# Sheet2.net
KiCad netlist of a schematic drawn in Altium Designer
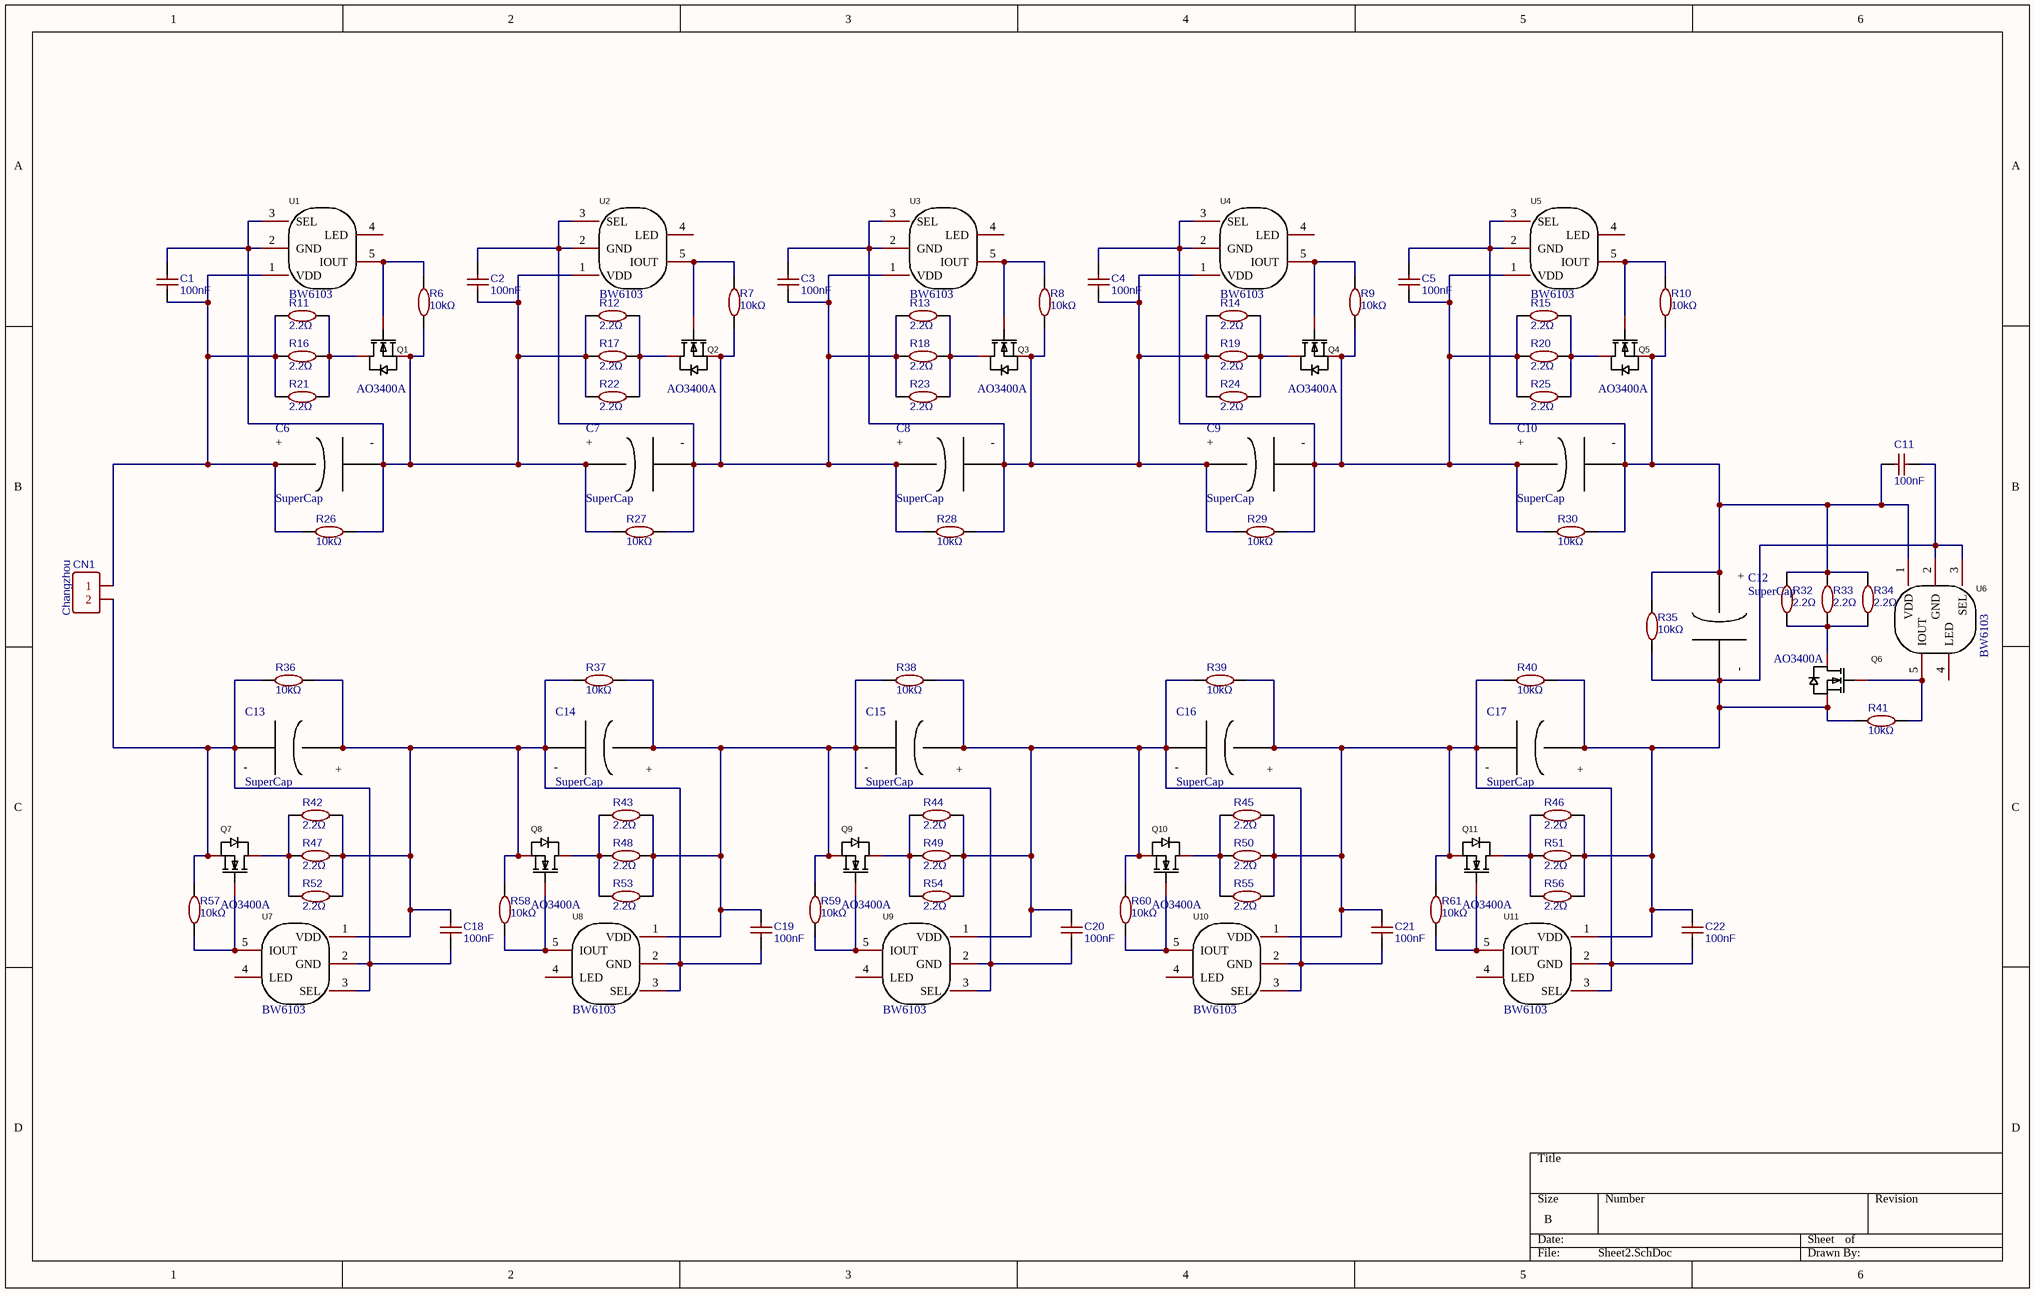
[diagram p0: Sheet2.SchDoc]

(export (version "E")
  (design (tool "Eeschema 10.0.6"))
  (components
    (comp (ref "C1")
      (value "100nF")
      (footprint "C-RAD-0603")
      (fields
        (field (name "BOM_SUPPLIER PART") "C157687")
        (field (name "BOM_MANUFACTURER PART") "0805CG330J500NT")
        (field (name "CONTRIBUTOR") "LCSC")
      )
      (libsource (lib "commonRC") (part "100nF"))
    )
    (comp (ref "C2")
      (value "100nF")
      (footprint "C-RAD-0603")
      (fields
        (field (name "BOM_SUPPLIER PART") "C157687")
        (field (name "BOM_MANUFACTURER PART") "0805CG330J500NT")
        (field (name "CONTRIBUTOR") "LCSC")
      )
      (libsource (lib "commonRC") (part "100nF"))
    )
    (comp (ref "C3")
      (value "100nF")
      (footprint "C-RAD-0603")
      (fields
        (field (name "BOM_SUPPLIER PART") "C157687")
        (field (name "BOM_MANUFACTURER PART") "0805CG330J500NT")
        (field (name "CONTRIBUTOR") "LCSC")
      )
      (libsource (lib "commonRC") (part "100nF"))
    )
    (comp (ref "C4")
      (value "100nF")
      (footprint "C-RAD-0603")
      (fields
        (field (name "BOM_SUPPLIER PART") "C157687")
        (field (name "BOM_MANUFACTURER PART") "0805CG330J500NT")
        (field (name "CONTRIBUTOR") "LCSC")
      )
      (libsource (lib "commonRC") (part "100nF"))
    )
    (comp (ref "C5")
      (value "100nF")
      (footprint "C-RAD-0603")
      (fields
        (field (name "BOM_SUPPLIER PART") "C157687")
        (field (name "BOM_MANUFACTURER PART") "0805CG330J500NT")
        (field (name "CONTRIBUTOR") "LCSC")
      )
      (libsource (lib "commonRC") (part "100nF"))
    )
    (comp (ref "C6")
      (value "SuperCap")
      (footprint "C_supercap1")
      (libsource (lib "Schlib1") (part "50F 2.7v"))
    )
    (comp (ref "C7")
      (value "SuperCap")
      (footprint "C_supercap1")
      (libsource (lib "Schlib1") (part "50F 2.7v"))
    )
    (comp (ref "C8")
      (value "SuperCap")
      (footprint "C_supercap1")
      (libsource (lib "Schlib1") (part "50F 2.7v"))
    )
    (comp (ref "C9")
      (value "SuperCap")
      (footprint "C_supercap1")
      (libsource (lib "Schlib1") (part "50F 2.7v"))
    )
    (comp (ref "C10")
      (value "SuperCap")
      (footprint "C_supercap1")
      (libsource (lib "Schlib1") (part "50F 2.7v"))
    )
    (comp (ref "C11")
      (value "100nF")
      (footprint "C-RAD-0603")
      (fields
        (field (name "BOM_SUPPLIER PART") "C157687")
        (field (name "BOM_MANUFACTURER PART") "0805CG330J500NT")
        (field (name "CONTRIBUTOR") "LCSC")
      )
      (libsource (lib "commonRC") (part "100nF"))
    )
    (comp (ref "C12") (value "SuperCap") (footprint "C_supercap1") (libsource (lib "") (part "50F 2.7v_1")))
    (comp (ref "C13")
      (value "SuperCap")
      (footprint "C_supercap1")
      (libsource (lib "Schlib1") (part "50F 2.7v"))
    )
    (comp (ref "C14")
      (value "SuperCap")
      (footprint "C_supercap1")
      (libsource (lib "Schlib1") (part "50F 2.7v"))
    )
    (comp (ref "C15")
      (value "SuperCap")
      (footprint "C_supercap1")
      (libsource (lib "Schlib1") (part "50F 2.7v"))
    )
    (comp (ref "C16")
      (value "SuperCap")
      (footprint "C_supercap1")
      (libsource (lib "Schlib1") (part "50F 2.7v"))
    )
    (comp (ref "C17")
      (value "SuperCap")
      (footprint "C_supercap1")
      (libsource (lib "Schlib1") (part "50F 2.7v"))
    )
    (comp (ref "C18")
      (value "100nF")
      (footprint "C-RAD-0603")
      (fields
        (field (name "BOM_SUPPLIER PART") "C157687")
        (field (name "BOM_MANUFACTURER PART") "0805CG330J500NT")
        (field (name "CONTRIBUTOR") "LCSC")
      )
      (libsource (lib "commonRC") (part "100nF"))
    )
    (comp (ref "C19")
      (value "100nF")
      (footprint "C-RAD-0603")
      (fields
        (field (name "BOM_SUPPLIER PART") "C157687")
        (field (name "BOM_MANUFACTURER PART") "0805CG330J500NT")
        (field (name "CONTRIBUTOR") "LCSC")
      )
      (libsource (lib "commonRC") (part "100nF"))
    )
    (comp (ref "C20")
      (value "100nF")
      (footprint "C-RAD-0603")
      (fields
        (field (name "BOM_SUPPLIER PART") "C157687")
        (field (name "BOM_MANUFACTURER PART") "0805CG330J500NT")
        (field (name "CONTRIBUTOR") "LCSC")
      )
      (libsource (lib "commonRC") (part "100nF"))
    )
    (comp (ref "C21")
      (value "100nF")
      (footprint "C-RAD-0603")
      (fields
        (field (name "BOM_SUPPLIER PART") "C157687")
        (field (name "BOM_MANUFACTURER PART") "0805CG330J500NT")
        (field (name "CONTRIBUTOR") "LCSC")
      )
      (libsource (lib "commonRC") (part "100nF"))
    )
    (comp (ref "C22")
      (value "100nF")
      (footprint "C-RAD-0603")
      (fields
        (field (name "BOM_SUPPLIER PART") "C157687")
        (field (name "BOM_MANUFACTURER PART") "0805CG330J500NT")
        (field (name "CONTRIBUTOR") "LCSC")
      )
      (libsource (lib "commonRC") (part "100nF"))
    )
    (comp (ref "CN1")
      (value "Changzhou")
      (footprint "CONN-TH_XT30UPB-F")
      (fields
        (field (name "BOM_SUPPLIER PART") "C108769")
        (field (name "BOM_MANUFACTURER PART") "XT30UPB-F")
        (field (name "CONTRIBUTOR") "LCSC")
      )
      (libsource (lib "Schlib1") (part "Changzhou"))
    )
    (comp (ref "Q1")
      (value "AO3400A")
      (footprint "SOT-23")
      (fields (field (name "MANUFACTURER") "AOS"))
      (libsource (lib "Schlib1") (part "AO3400A_C20917"))
    )
    (comp (ref "Q2")
      (value "AO3400A")
      (footprint "SOT-23")
      (fields (field (name "MANUFACTURER") "AOS"))
      (libsource (lib "Schlib1") (part "AO3400A_C20917"))
    )
    (comp (ref "Q3")
      (value "AO3400A")
      (footprint "SOT-23")
      (fields (field (name "MANUFACTURER") "AOS"))
      (libsource (lib "Schlib1") (part "AO3400A_C20917"))
    )
    (comp (ref "Q4")
      (value "AO3400A")
      (footprint "SOT-23")
      (fields (field (name "MANUFACTURER") "AOS"))
      (libsource (lib "Schlib1") (part "AO3400A_C20917"))
    )
    (comp (ref "Q5")
      (value "AO3400A")
      (footprint "SOT-23")
      (fields (field (name "MANUFACTURER") "AOS"))
      (libsource (lib "Schlib1") (part "AO3400A_C20917"))
    )
    (comp (ref "Q6")
      (value "AO3400A")
      (footprint "SOT-23")
      (fields (field (name "MANUFACTURER") "AOS"))
      (libsource (lib "Schlib1") (part "AO3400A_C20917"))
    )
    (comp (ref "Q7")
      (value "AO3400A")
      (footprint "SOT-23")
      (fields (field (name "MANUFACTURER") "AOS"))
      (libsource (lib "Schlib1") (part "AO3400A_C20917"))
    )
    (comp (ref "Q8")
      (value "AO3400A")
      (footprint "SOT-23")
      (fields (field (name "MANUFACTURER") "AOS"))
      (libsource (lib "Schlib1") (part "AO3400A_C20917"))
    )
    (comp (ref "Q9")
      (value "AO3400A")
      (footprint "SOT-23")
      (fields (field (name "MANUFACTURER") "AOS"))
      (libsource (lib "Schlib1") (part "AO3400A_C20917"))
    )
    (comp (ref "Q10")
      (value "AO3400A")
      (footprint "SOT-23")
      (fields (field (name "MANUFACTURER") "AOS"))
      (libsource (lib "Schlib1") (part "AO3400A_C20917"))
    )
    (comp (ref "Q11")
      (value "AO3400A")
      (footprint "SOT-23")
      (fields (field (name "MANUFACTURER") "AOS"))
      (libsource (lib "Schlib1") (part "AO3400A_C20917"))
    )
    (comp (ref "R6")
      (value "10kΩ")
      (footprint "0603-1")
      (fields
        (field (name "BOM_MANUFACTURER PART") "0603WAF1002T5E")
        (field (name "BOM_SUPPLIER PART") "C25804")
      )
      (libsource (lib "commonRC") (part "10kΩ"))
    )
    (comp (ref "R7")
      (value "10kΩ")
      (footprint "0603-1")
      (fields
        (field (name "BOM_MANUFACTURER PART") "0603WAF1002T5E")
        (field (name "BOM_SUPPLIER PART") "C25804")
      )
      (libsource (lib "commonRC") (part "10kΩ"))
    )
    (comp (ref "R8")
      (value "10kΩ")
      (footprint "0603-1")
      (fields
        (field (name "BOM_MANUFACTURER PART") "0603WAF1002T5E")
        (field (name "BOM_SUPPLIER PART") "C25804")
      )
      (libsource (lib "commonRC") (part "10kΩ"))
    )
    (comp (ref "R9")
      (value "10kΩ")
      (footprint "0603-1")
      (fields
        (field (name "BOM_MANUFACTURER PART") "0603WAF1002T5E")
        (field (name "BOM_SUPPLIER PART") "C25804")
      )
      (libsource (lib "commonRC") (part "10kΩ"))
    )
    (comp (ref "R10")
      (value "10kΩ")
      (footprint "0603-1")
      (fields
        (field (name "BOM_MANUFACTURER PART") "0603WAF1002T5E")
        (field (name "BOM_SUPPLIER PART") "C25804")
      )
      (libsource (lib "commonRC") (part "10kΩ"))
    )
    (comp (ref "R11")
      (value "2.2Ω")
      (footprint "2512")
      (fields
        (field (name "BOM_MANUFACTURER PART") "0603WAF1002T5E")
        (field (name "BOM_SUPPLIER PART") "C25804")
      )
      (libsource (lib "Schlib1") (part "2.2Ω_2512"))
    )
    (comp (ref "R12")
      (value "2.2Ω")
      (footprint "2512")
      (fields
        (field (name "BOM_MANUFACTURER PART") "0603WAF1002T5E")
        (field (name "BOM_SUPPLIER PART") "C25804")
      )
      (libsource (lib "Schlib1") (part "2.2Ω_2512"))
    )
    (comp (ref "R13")
      (value "2.2Ω")
      (footprint "2512")
      (fields
        (field (name "BOM_MANUFACTURER PART") "0603WAF1002T5E")
        (field (name "BOM_SUPPLIER PART") "C25804")
      )
      (libsource (lib "Schlib1") (part "2.2Ω_2512"))
    )
    (comp (ref "R14")
      (value "2.2Ω")
      (footprint "2512")
      (fields
        (field (name "BOM_MANUFACTURER PART") "0603WAF1002T5E")
        (field (name "BOM_SUPPLIER PART") "C25804")
      )
      (libsource (lib "Schlib1") (part "2.2Ω_2512"))
    )
    (comp (ref "R15")
      (value "2.2Ω")
      (footprint "2512")
      (fields
        (field (name "BOM_MANUFACTURER PART") "0603WAF1002T5E")
        (field (name "BOM_SUPPLIER PART") "C25804")
      )
      (libsource (lib "Schlib1") (part "2.2Ω_2512"))
    )
    (comp (ref "R16")
      (value "2.2Ω")
      (footprint "2512")
      (fields
        (field (name "BOM_MANUFACTURER PART") "0603WAF1002T5E")
        (field (name "BOM_SUPPLIER PART") "C25804")
      )
      (libsource (lib "Schlib1") (part "2.2Ω_2512"))
    )
    (comp (ref "R17")
      (value "2.2Ω")
      (footprint "2512")
      (fields
        (field (name "BOM_MANUFACTURER PART") "0603WAF1002T5E")
        (field (name "BOM_SUPPLIER PART") "C25804")
      )
      (libsource (lib "Schlib1") (part "2.2Ω_2512"))
    )
    (comp (ref "R18")
      (value "2.2Ω")
      (footprint "2512")
      (fields
        (field (name "BOM_MANUFACTURER PART") "0603WAF1002T5E")
        (field (name "BOM_SUPPLIER PART") "C25804")
      )
      (libsource (lib "Schlib1") (part "2.2Ω_2512"))
    )
    (comp (ref "R19")
      (value "2.2Ω")
      (footprint "2512")
      (fields
        (field (name "BOM_MANUFACTURER PART") "0603WAF1002T5E")
        (field (name "BOM_SUPPLIER PART") "C25804")
      )
      (libsource (lib "Schlib1") (part "2.2Ω_2512"))
    )
    (comp (ref "R20")
      (value "2.2Ω")
      (footprint "2512")
      (fields
        (field (name "BOM_MANUFACTURER PART") "0603WAF1002T5E")
        (field (name "BOM_SUPPLIER PART") "C25804")
      )
      (libsource (lib "Schlib1") (part "2.2Ω_2512"))
    )
    (comp (ref "R21")
      (value "2.2Ω")
      (footprint "2512")
      (fields
        (field (name "BOM_MANUFACTURER PART") "0603WAF1002T5E")
        (field (name "BOM_SUPPLIER PART") "C25804")
      )
      (libsource (lib "Schlib1") (part "2.2Ω_2512"))
    )
    (comp (ref "R22")
      (value "2.2Ω")
      (footprint "2512")
      (fields
        (field (name "BOM_MANUFACTURER PART") "0603WAF1002T5E")
        (field (name "BOM_SUPPLIER PART") "C25804")
      )
      (libsource (lib "Schlib1") (part "2.2Ω_2512"))
    )
    (comp (ref "R23")
      (value "2.2Ω")
      (footprint "2512")
      (fields
        (field (name "BOM_MANUFACTURER PART") "0603WAF1002T5E")
        (field (name "BOM_SUPPLIER PART") "C25804")
      )
      (libsource (lib "Schlib1") (part "2.2Ω_2512"))
    )
    (comp (ref "R24")
      (value "2.2Ω")
      (footprint "2512")
      (fields
        (field (name "BOM_MANUFACTURER PART") "0603WAF1002T5E")
        (field (name "BOM_SUPPLIER PART") "C25804")
      )
      (libsource (lib "Schlib1") (part "2.2Ω_2512"))
    )
    (comp (ref "R25")
      (value "2.2Ω")
      (footprint "2512")
      (fields
        (field (name "BOM_MANUFACTURER PART") "0603WAF1002T5E")
        (field (name "BOM_SUPPLIER PART") "C25804")
      )
      (libsource (lib "Schlib1") (part "2.2Ω_2512"))
    )
    (comp (ref "R26")
      (value "10kΩ")
      (footprint "0603-1")
      (fields
        (field (name "BOM_MANUFACTURER PART") "0603WAF1002T5E")
        (field (name "BOM_SUPPLIER PART") "C25804")
      )
      (libsource (lib "commonRC") (part "10kΩ"))
    )
    (comp (ref "R27")
      (value "10kΩ")
      (footprint "0603-1")
      (fields
        (field (name "BOM_MANUFACTURER PART") "0603WAF1002T5E")
        (field (name "BOM_SUPPLIER PART") "C25804")
      )
      (libsource (lib "commonRC") (part "10kΩ"))
    )
    (comp (ref "R28")
      (value "10kΩ")
      (footprint "0603-1")
      (fields
        (field (name "BOM_MANUFACTURER PART") "0603WAF1002T5E")
        (field (name "BOM_SUPPLIER PART") "C25804")
      )
      (libsource (lib "commonRC") (part "10kΩ"))
    )
    (comp (ref "R29")
      (value "10kΩ")
      (footprint "0603-1")
      (fields
        (field (name "BOM_MANUFACTURER PART") "0603WAF1002T5E")
        (field (name "BOM_SUPPLIER PART") "C25804")
      )
      (libsource (lib "commonRC") (part "10kΩ"))
    )
    (comp (ref "R30")
      (value "10kΩ")
      (footprint "0603-1")
      (fields
        (field (name "BOM_MANUFACTURER PART") "0603WAF1002T5E")
        (field (name "BOM_SUPPLIER PART") "C25804")
      )
      (libsource (lib "commonRC") (part "10kΩ"))
    )
    (comp (ref "R32")
      (value "2.2Ω")
      (footprint "2512")
      (fields
        (field (name "BOM_MANUFACTURER PART") "0603WAF1002T5E")
        (field (name "BOM_SUPPLIER PART") "C25804")
      )
      (libsource (lib "Schlib1") (part "2.2Ω_2512"))
    )
    (comp (ref "R33")
      (value "2.2Ω")
      (footprint "2512")
      (fields
        (field (name "BOM_MANUFACTURER PART") "0603WAF1002T5E")
        (field (name "BOM_SUPPLIER PART") "C25804")
      )
      (libsource (lib "Schlib1") (part "2.2Ω_2512"))
    )
    (comp (ref "R34")
      (value "2.2Ω")
      (footprint "2512")
      (fields
        (field (name "BOM_MANUFACTURER PART") "0603WAF1002T5E")
        (field (name "BOM_SUPPLIER PART") "C25804")
      )
      (libsource (lib "Schlib1") (part "2.2Ω_2512"))
    )
    (comp (ref "R35")
      (value "10kΩ")
      (footprint "0603-1")
      (fields
        (field (name "BOM_MANUFACTURER PART") "0603WAF1002T5E")
        (field (name "BOM_SUPPLIER PART") "C25804")
      )
      (libsource (lib "commonRC") (part "10kΩ"))
    )
    (comp (ref "R36")
      (value "10kΩ")
      (footprint "0603-1")
      (fields
        (field (name "BOM_MANUFACTURER PART") "0603WAF1002T5E")
        (field (name "BOM_SUPPLIER PART") "C25804")
      )
      (libsource (lib "commonRC") (part "10kΩ"))
    )
    (comp (ref "R37")
      (value "10kΩ")
      (footprint "0603-1")
      (fields
        (field (name "BOM_MANUFACTURER PART") "0603WAF1002T5E")
        (field (name "BOM_SUPPLIER PART") "C25804")
      )
      (libsource (lib "commonRC") (part "10kΩ"))
    )
    (comp (ref "R38")
      (value "10kΩ")
      (footprint "0603-1")
      (fields
        (field (name "BOM_MANUFACTURER PART") "0603WAF1002T5E")
        (field (name "BOM_SUPPLIER PART") "C25804")
      )
      (libsource (lib "commonRC") (part "10kΩ"))
    )
    (comp (ref "R39")
      (value "10kΩ")
      (footprint "0603-1")
      (fields
        (field (name "BOM_MANUFACTURER PART") "0603WAF1002T5E")
        (field (name "BOM_SUPPLIER PART") "C25804")
      )
      (libsource (lib "commonRC") (part "10kΩ"))
    )
    (comp (ref "R40")
      (value "10kΩ")
      (footprint "0603-1")
      (fields
        (field (name "BOM_MANUFACTURER PART") "0603WAF1002T5E")
        (field (name "BOM_SUPPLIER PART") "C25804")
      )
      (libsource (lib "commonRC") (part "10kΩ"))
    )
    (comp (ref "R41")
      (value "10kΩ")
      (footprint "0603-1")
      (fields
        (field (name "BOM_MANUFACTURER PART") "0603WAF1002T5E")
        (field (name "BOM_SUPPLIER PART") "C25804")
      )
      (libsource (lib "commonRC") (part "10kΩ"))
    )
    (comp (ref "R42")
      (value "2.2Ω")
      (footprint "2512")
      (fields
        (field (name "BOM_MANUFACTURER PART") "0603WAF1002T5E")
        (field (name "BOM_SUPPLIER PART") "C25804")
      )
      (libsource (lib "Schlib1") (part "2.2Ω_2512"))
    )
    (comp (ref "R43")
      (value "2.2Ω")
      (footprint "2512")
      (fields
        (field (name "BOM_MANUFACTURER PART") "0603WAF1002T5E")
        (field (name "BOM_SUPPLIER PART") "C25804")
      )
      (libsource (lib "Schlib1") (part "2.2Ω_2512"))
    )
    (comp (ref "R44")
      (value "2.2Ω")
      (footprint "2512")
      (fields
        (field (name "BOM_MANUFACTURER PART") "0603WAF1002T5E")
        (field (name "BOM_SUPPLIER PART") "C25804")
      )
      (libsource (lib "Schlib1") (part "2.2Ω_2512"))
    )
    (comp (ref "R45")
      (value "2.2Ω")
      (footprint "2512")
      (fields
        (field (name "BOM_MANUFACTURER PART") "0603WAF1002T5E")
        (field (name "BOM_SUPPLIER PART") "C25804")
      )
      (libsource (lib "Schlib1") (part "2.2Ω_2512"))
    )
    (comp (ref "R46")
      (value "2.2Ω")
      (footprint "2512")
      (fields
        (field (name "BOM_MANUFACTURER PART") "0603WAF1002T5E")
        (field (name "BOM_SUPPLIER PART") "C25804")
      )
      (libsource (lib "Schlib1") (part "2.2Ω_2512"))
    )
    (comp (ref "R47")
      (value "2.2Ω")
      (footprint "2512")
      (fields
        (field (name "BOM_MANUFACTURER PART") "0603WAF1002T5E")
        (field (name "BOM_SUPPLIER PART") "C25804")
      )
      (libsource (lib "Schlib1") (part "2.2Ω_2512"))
    )
    (comp (ref "R48")
      (value "2.2Ω")
      (footprint "2512")
      (fields
        (field (name "BOM_MANUFACTURER PART") "0603WAF1002T5E")
        (field (name "BOM_SUPPLIER PART") "C25804")
      )
      (libsource (lib "Schlib1") (part "2.2Ω_2512"))
    )
    (comp (ref "R49")
      (value "2.2Ω")
      (footprint "2512")
      (fields
        (field (name "BOM_MANUFACTURER PART") "0603WAF1002T5E")
        (field (name "BOM_SUPPLIER PART") "C25804")
      )
      (libsource (lib "Schlib1") (part "2.2Ω_2512"))
    )
    (comp (ref "R50")
      (value "2.2Ω")
      (footprint "2512")
      (fields
        (field (name "BOM_MANUFACTURER PART") "0603WAF1002T5E")
        (field (name "BOM_SUPPLIER PART") "C25804")
      )
      (libsource (lib "Schlib1") (part "2.2Ω_2512"))
    )
    (comp (ref "R51")
      (value "2.2Ω")
      (footprint "2512")
      (fields
        (field (name "BOM_MANUFACTURER PART") "0603WAF1002T5E")
        (field (name "BOM_SUPPLIER PART") "C25804")
      )
      (libsource (lib "Schlib1") (part "2.2Ω_2512"))
    )
    (comp (ref "R52")
      (value "2.2Ω")
      (footprint "2512")
      (fields
        (field (name "BOM_MANUFACTURER PART") "0603WAF1002T5E")
        (field (name "BOM_SUPPLIER PART") "C25804")
      )
      (libsource (lib "Schlib1") (part "2.2Ω_2512"))
    )
    (comp (ref "R53")
      (value "2.2Ω")
      (footprint "2512")
      (fields
        (field (name "BOM_MANUFACTURER PART") "0603WAF1002T5E")
        (field (name "BOM_SUPPLIER PART") "C25804")
      )
      (libsource (lib "Schlib1") (part "2.2Ω_2512"))
    )
    (comp (ref "R54")
      (value "2.2Ω")
      (footprint "2512")
      (fields
        (field (name "BOM_MANUFACTURER PART") "0603WAF1002T5E")
        (field (name "BOM_SUPPLIER PART") "C25804")
      )
      (libsource (lib "Schlib1") (part "2.2Ω_2512"))
    )
    (comp (ref "R55")
      (value "2.2Ω")
      (footprint "2512")
      (fields
        (field (name "BOM_MANUFACTURER PART") "0603WAF1002T5E")
        (field (name "BOM_SUPPLIER PART") "C25804")
      )
      (libsource (lib "Schlib1") (part "2.2Ω_2512"))
    )
    (comp (ref "R56")
      (value "2.2Ω")
      (footprint "2512")
      (fields
        (field (name "BOM_MANUFACTURER PART") "0603WAF1002T5E")
        (field (name "BOM_SUPPLIER PART") "C25804")
      )
      (libsource (lib "Schlib1") (part "2.2Ω_2512"))
    )
    (comp (ref "R57")
      (value "10kΩ")
      (footprint "0603-1")
      (fields
        (field (name "BOM_MANUFACTURER PART") "0603WAF1002T5E")
        (field (name "BOM_SUPPLIER PART") "C25804")
      )
      (libsource (lib "commonRC") (part "10kΩ"))
    )
    (comp (ref "R58")
      (value "10kΩ")
      (footprint "0603-1")
      (fields
        (field (name "BOM_MANUFACTURER PART") "0603WAF1002T5E")
        (field (name "BOM_SUPPLIER PART") "C25804")
      )
      (libsource (lib "commonRC") (part "10kΩ"))
    )
    (comp (ref "R59")
      (value "10kΩ")
      (footprint "0603-1")
      (fields
        (field (name "BOM_MANUFACTURER PART") "0603WAF1002T5E")
        (field (name "BOM_SUPPLIER PART") "C25804")
      )
      (libsource (lib "commonRC") (part "10kΩ"))
    )
    (comp (ref "R60")
      (value "10kΩ")
      (footprint "0603-1")
      (fields
        (field (name "BOM_MANUFACTURER PART") "0603WAF1002T5E")
        (field (name "BOM_SUPPLIER PART") "C25804")
      )
      (libsource (lib "commonRC") (part "10kΩ"))
    )
    (comp (ref "R61")
      (value "10kΩ")
      (footprint "0603-1")
      (fields
        (field (name "BOM_MANUFACTURER PART") "0603WAF1002T5E")
        (field (name "BOM_SUPPLIER PART") "C25804")
      )
      (libsource (lib "commonRC") (part "10kΩ"))
    )
    (comp (ref "U1")
      (value "BW6103")
      (footprint "SOT-23-5_L3.0-W1.7-P0.95-LS2.8-BL")
      (fields (field (name "MANUFACTURER") "RICHTEK(台湾立锜)") (field (name "MANUFACTURER PART") "RT9013-33GB"))
      (libsource (lib "Schlib1") (part "BW6103"))
    )
    (comp (ref "U2")
      (value "BW6103")
      (footprint "SOT-23-5_L3.0-W1.7-P0.95-LS2.8-BL")
      (fields (field (name "MANUFACTURER") "RICHTEK(台湾立锜)") (field (name "MANUFACTURER PART") "RT9013-33GB"))
      (libsource (lib "Schlib1") (part "BW6103"))
    )
    (comp (ref "U3")
      (value "BW6103")
      (footprint "SOT-23-5_L3.0-W1.7-P0.95-LS2.8-BL")
      (fields (field (name "MANUFACTURER") "RICHTEK(台湾立锜)") (field (name "MANUFACTURER PART") "RT9013-33GB"))
      (libsource (lib "Schlib1") (part "BW6103"))
    )
    (comp (ref "U4")
      (value "BW6103")
      (footprint "SOT-23-5_L3.0-W1.7-P0.95-LS2.8-BL")
      (fields (field (name "MANUFACTURER") "RICHTEK(台湾立锜)") (field (name "MANUFACTURER PART") "RT9013-33GB"))
      (libsource (lib "Schlib1") (part "BW6103"))
    )
    (comp (ref "U5")
      (value "BW6103")
      (footprint "SOT-23-5_L3.0-W1.7-P0.95-LS2.8-BL")
      (fields (field (name "MANUFACTURER") "RICHTEK(台湾立锜)") (field (name "MANUFACTURER PART") "RT9013-33GB"))
      (libsource (lib "Schlib1") (part "BW6103"))
    )
    (comp (ref "U6")
      (value "BW6103")
      (footprint "SOT-23-5_L3.0-W1.7-P0.95-LS2.8-BL")
      (fields (field (name "MANUFACTURER") "RICHTEK(台湾立锜)") (field (name "MANUFACTURER PART") "RT9013-33GB"))
      (libsource (lib "Schlib1") (part "BW6103"))
    )
    (comp (ref "U7")
      (value "BW6103")
      (footprint "SOT-23-5_L3.0-W1.7-P0.95-LS2.8-BL")
      (fields (field (name "MANUFACTURER") "RICHTEK(台湾立锜)") (field (name "MANUFACTURER PART") "RT9013-33GB"))
      (libsource (lib "Schlib1") (part "BW6103"))
    )
    (comp (ref "U8")
      (value "BW6103")
      (footprint "SOT-23-5_L3.0-W1.7-P0.95-LS2.8-BL")
      (fields (field (name "MANUFACTURER") "RICHTEK(台湾立锜)") (field (name "MANUFACTURER PART") "RT9013-33GB"))
      (libsource (lib "Schlib1") (part "BW6103"))
    )
    (comp (ref "U9")
      (value "BW6103")
      (footprint "SOT-23-5_L3.0-W1.7-P0.95-LS2.8-BL")
      (fields (field (name "MANUFACTURER") "RICHTEK(台湾立锜)") (field (name "MANUFACTURER PART") "RT9013-33GB"))
      (libsource (lib "Schlib1") (part "BW6103"))
    )
    (comp (ref "U10")
      (value "BW6103")
      (footprint "SOT-23-5_L3.0-W1.7-P0.95-LS2.8-BL")
      (fields (field (name "MANUFACTURER") "RICHTEK(台湾立锜)") (field (name "MANUFACTURER PART") "RT9013-33GB"))
      (libsource (lib "Schlib1") (part "BW6103"))
    )
    (comp (ref "U11")
      (value "BW6103")
      (footprint "SOT-23-5_L3.0-W1.7-P0.95-LS2.8-BL")
      (fields (field (name "MANUFACTURER") "RICHTEK(台湾立锜)") (field (name "MANUFACTURER PART") "RT9013-33GB"))
      (libsource (lib "Schlib1") (part "BW6103"))
    )
  )
  (nets
    (net (code "1") (name "Net-(Q1-D)") (class "Default")
      (node (ref "Q1") (pin "3") (pinfunction "D_3") (pintype "passive"))
      (node (ref "R11") (pin "1") (pinfunction "1_1") (pintype "passive"))
      (node (ref "R16") (pin "1") (pinfunction "1_1") (pintype "passive"))
      (node (ref "R21") (pin "1") (pinfunction "1_1") (pintype "passive"))
    )
    (net (code "2") (name "Net-(Q1-G)") (class "Default")
      (node (ref "Q1") (pin "1") (pinfunction "G_1") (pintype "passive"))
      (node (ref "R6") (pin "2") (pinfunction "2_2") (pintype "passive"))
      (node (ref "U1") (pin "5") (pinfunction "IOUT_5") (pintype "passive"))
    )
    (net (code "3") (name "Net-(Q1-S)") (class "Default")
      (node (ref "C1") (pin "2") (pinfunction "2_2") (pintype "passive"))
      (node (ref "C2") (pin "1") (pinfunction "1_1") (pintype "passive"))
      (node (ref "C6") (pin "2") (pinfunction "2_2") (pintype "passive"))
      (node (ref "C7") (pin "1") (pinfunction "1_1") (pintype "passive"))
      (node (ref "Q1") (pin "2") (pinfunction "S_2") (pintype "passive"))
      (node (ref "R12") (pin "2") (pinfunction "2_2") (pintype "passive"))
      (node (ref "R17") (pin "2") (pinfunction "2_2") (pintype "passive"))
      (node (ref "R22") (pin "2") (pinfunction "2_2") (pintype "passive"))
      (node (ref "R26") (pin "2") (pinfunction "2_2") (pintype "passive"))
      (node (ref "R27") (pin "1") (pinfunction "1_1") (pintype "passive"))
      (node (ref "R6") (pin "1") (pinfunction "1_1") (pintype "passive"))
      (node (ref "U1") (pin "2") (pinfunction "GND_2") (pintype "passive"))
      (node (ref "U1") (pin "3") (pinfunction "SEL_3") (pintype "passive"))
      (node (ref "U2") (pin "1") (pinfunction "VDD_1") (pintype "passive"))
    )
    (net (code "4") (name "Net-(Q2-D)") (class "Default")
      (node (ref "Q2") (pin "3") (pinfunction "D_3") (pintype "passive"))
      (node (ref "R12") (pin "1") (pinfunction "1_1") (pintype "passive"))
      (node (ref "R17") (pin "1") (pinfunction "1_1") (pintype "passive"))
      (node (ref "R22") (pin "1") (pinfunction "1_1") (pintype "passive"))
    )
    (net (code "5") (name "Net-(Q2-G)") (class "Default")
      (node (ref "Q2") (pin "1") (pinfunction "G_1") (pintype "passive"))
      (node (ref "R7") (pin "2") (pinfunction "2_2") (pintype "passive"))
      (node (ref "U2") (pin "5") (pinfunction "IOUT_5") (pintype "passive"))
    )
    (net (code "6") (name "Net-(Q2-S)") (class "Default")
      (node (ref "C2") (pin "2") (pinfunction "2_2") (pintype "passive"))
      (node (ref "C3") (pin "1") (pinfunction "1_1") (pintype "passive"))
      (node (ref "C7") (pin "2") (pinfunction "2_2") (pintype "passive"))
      (node (ref "C8") (pin "1") (pinfunction "1_1") (pintype "passive"))
      (node (ref "Q2") (pin "2") (pinfunction "S_2") (pintype "passive"))
      (node (ref "R13") (pin "2") (pinfunction "2_2") (pintype "passive"))
      (node (ref "R18") (pin "2") (pinfunction "2_2") (pintype "passive"))
      (node (ref "R23") (pin "2") (pinfunction "2_2") (pintype "passive"))
      (node (ref "R27") (pin "2") (pinfunction "2_2") (pintype "passive"))
      (node (ref "R28") (pin "1") (pinfunction "1_1") (pintype "passive"))
      (node (ref "R7") (pin "1") (pinfunction "1_1") (pintype "passive"))
      (node (ref "U2") (pin "2") (pinfunction "GND_2") (pintype "passive"))
      (node (ref "U2") (pin "3") (pinfunction "SEL_3") (pintype "passive"))
      (node (ref "U3") (pin "1") (pinfunction "VDD_1") (pintype "passive"))
    )
    (net (code "7") (name "Net-(Q3-D)") (class "Default")
      (node (ref "Q3") (pin "3") (pinfunction "D_3") (pintype "passive"))
      (node (ref "R13") (pin "1") (pinfunction "1_1") (pintype "passive"))
      (node (ref "R18") (pin "1") (pinfunction "1_1") (pintype "passive"))
      (node (ref "R23") (pin "1") (pinfunction "1_1") (pintype "passive"))
    )
    (net (code "8") (name "Net-(Q3-G)") (class "Default")
      (node (ref "Q3") (pin "1") (pinfunction "G_1") (pintype "passive"))
      (node (ref "R8") (pin "2") (pinfunction "2_2") (pintype "passive"))
      (node (ref "U3") (pin "5") (pinfunction "IOUT_5") (pintype "passive"))
    )
    (net (code "9") (name "Net-(Q3-S)") (class "Default")
      (node (ref "C3") (pin "2") (pinfunction "2_2") (pintype "passive"))
      (node (ref "C4") (pin "1") (pinfunction "1_1") (pintype "passive"))
      (node (ref "C8") (pin "2") (pinfunction "2_2") (pintype "passive"))
      (node (ref "C9") (pin "1") (pinfunction "1_1") (pintype "passive"))
      (node (ref "Q3") (pin "2") (pinfunction "S_2") (pintype "passive"))
      (node (ref "R14") (pin "2") (pinfunction "2_2") (pintype "passive"))
      (node (ref "R19") (pin "2") (pinfunction "2_2") (pintype "passive"))
      (node (ref "R24") (pin "2") (pinfunction "2_2") (pintype "passive"))
      (node (ref "R28") (pin "2") (pinfunction "2_2") (pintype "passive"))
      (node (ref "R29") (pin "1") (pinfunction "1_1") (pintype "passive"))
      (node (ref "R8") (pin "1") (pinfunction "1_1") (pintype "passive"))
      (node (ref "U3") (pin "2") (pinfunction "GND_2") (pintype "passive"))
      (node (ref "U3") (pin "3") (pinfunction "SEL_3") (pintype "passive"))
      (node (ref "U4") (pin "1") (pinfunction "VDD_1") (pintype "passive"))
    )
    (net (code "10") (name "Net-(Q4-D)") (class "Default")
      (node (ref "Q4") (pin "3") (pinfunction "D_3") (pintype "passive"))
      (node (ref "R14") (pin "1") (pinfunction "1_1") (pintype "passive"))
      (node (ref "R19") (pin "1") (pinfunction "1_1") (pintype "passive"))
      (node (ref "R24") (pin "1") (pinfunction "1_1") (pintype "passive"))
    )
    (net (code "11") (name "Net-(Q4-G)") (class "Default")
      (node (ref "Q4") (pin "1") (pinfunction "G_1") (pintype "passive"))
      (node (ref "R9") (pin "2") (pinfunction "2_2") (pintype "passive"))
      (node (ref "U4") (pin "5") (pinfunction "IOUT_5") (pintype "passive"))
    )
    (net (code "12") (name "Net-(Q4-S)") (class "Default")
      (node (ref "C10") (pin "1") (pinfunction "1_1") (pintype "passive"))
      (node (ref "C4") (pin "2") (pinfunction "2_2") (pintype "passive"))
      (node (ref "C5") (pin "1") (pinfunction "1_1") (pintype "passive"))
      (node (ref "C9") (pin "2") (pinfunction "2_2") (pintype "passive"))
      (node (ref "Q4") (pin "2") (pinfunction "S_2") (pintype "passive"))
      (node (ref "R15") (pin "2") (pinfunction "2_2") (pintype "passive"))
      (node (ref "R20") (pin "2") (pinfunction "2_2") (pintype "passive"))
      (node (ref "R25") (pin "2") (pinfunction "2_2") (pintype "passive"))
      (node (ref "R29") (pin "2") (pinfunction "2_2") (pintype "passive"))
      (node (ref "R30") (pin "1") (pinfunction "1_1") (pintype "passive"))
      (node (ref "R9") (pin "1") (pinfunction "1_1") (pintype "passive"))
      (node (ref "U4") (pin "2") (pinfunction "GND_2") (pintype "passive"))
      (node (ref "U4") (pin "3") (pinfunction "SEL_3") (pintype "passive"))
      (node (ref "U5") (pin "1") (pinfunction "VDD_1") (pintype "passive"))
    )
    (net (code "13") (name "Net-(Q5-D)") (class "Default")
      (node (ref "Q5") (pin "3") (pinfunction "D_3") (pintype "passive"))
      (node (ref "R15") (pin "1") (pinfunction "1_1") (pintype "passive"))
      (node (ref "R20") (pin "1") (pinfunction "1_1") (pintype "passive"))
      (node (ref "R25") (pin "1") (pinfunction "1_1") (pintype "passive"))
    )
    (net (code "14") (name "Net-(Q5-G)") (class "Default")
      (node (ref "Q5") (pin "1") (pinfunction "G_1") (pintype "passive"))
      (node (ref "R10") (pin "2") (pinfunction "2_2") (pintype "passive"))
      (node (ref "U5") (pin "5") (pinfunction "IOUT_5") (pintype "passive"))
    )
    (net (code "15") (name "Net-(Q5-S)") (class "Default")
      (node (ref "C10") (pin "2") (pinfunction "2_2") (pintype "passive"))
      (node (ref "C11") (pin "1") (pinfunction "1_1") (pintype "passive"))
      (node (ref "C12") (pin "1") (pinfunction "1_1") (pintype "passive"))
      (node (ref "C5") (pin "2") (pinfunction "2_2") (pintype "passive"))
      (node (ref "Q5") (pin "2") (pinfunction "S_2") (pintype "passive"))
      (node (ref "R10") (pin "1") (pinfunction "1_1") (pintype "passive"))
      (node (ref "R30") (pin "2") (pinfunction "2_2") (pintype "passive"))
      (node (ref "R32") (pin "2") (pinfunction "2_2") (pintype "passive"))
      (node (ref "R33") (pin "2") (pinfunction "2_2") (pintype "passive"))
      (node (ref "R34") (pin "2") (pinfunction "2_2") (pintype "passive"))
      (node (ref "R35") (pin "1") (pinfunction "1_1") (pintype "passive"))
      (node (ref "U5") (pin "2") (pinfunction "GND_2") (pintype "passive"))
      (node (ref "U5") (pin "3") (pinfunction "SEL_3") (pintype "passive"))
      (node (ref "U6") (pin "1") (pinfunction "VDD_1") (pintype "passive"))
    )
    (net (code "16") (name "Net-(Q6-D)") (class "Default")
      (node (ref "Q6") (pin "3") (pinfunction "D_3") (pintype "passive"))
      (node (ref "R32") (pin "1") (pinfunction "1_1") (pintype "passive"))
      (node (ref "R33") (pin "1") (pinfunction "1_1") (pintype "passive"))
      (node (ref "R34") (pin "1") (pinfunction "1_1") (pintype "passive"))
    )
    (net (code "17") (name "Net-(Q6-G)") (class "Default")
      (node (ref "Q6") (pin "1") (pinfunction "G_1") (pintype "passive"))
      (node (ref "R41") (pin "2") (pinfunction "2_2") (pintype "passive"))
      (node (ref "U6") (pin "5") (pinfunction "IOUT_5") (pintype "passive"))
    )
    (net (code "18") (name "Net-(Q6-S)") (class "Default")
      (node (ref "C11") (pin "2") (pinfunction "2_2") (pintype "passive"))
      (node (ref "C12") (pin "2") (pinfunction "2_2") (pintype "passive"))
      (node (ref "C17") (pin "1") (pinfunction "1_1") (pintype "passive"))
      (node (ref "C22") (pin "1") (pinfunction "1_1") (pintype "passive"))
      (node (ref "Q6") (pin "2") (pinfunction "S_2") (pintype "passive"))
      (node (ref "R35") (pin "2") (pinfunction "2_2") (pintype "passive"))
      (node (ref "R40") (pin "1") (pinfunction "1_1") (pintype "passive"))
      (node (ref "R41") (pin "1") (pinfunction "1_1") (pintype "passive"))
      (node (ref "R46") (pin "2") (pinfunction "2_2") (pintype "passive"))
      (node (ref "R51") (pin "2") (pinfunction "2_2") (pintype "passive"))
      (node (ref "R56") (pin "2") (pinfunction "2_2") (pintype "passive"))
      (node (ref "U11") (pin "1") (pinfunction "VDD_1") (pintype "passive"))
      (node (ref "U6") (pin "2") (pinfunction "GND_2") (pintype "passive"))
      (node (ref "U6") (pin "3") (pinfunction "SEL_3") (pintype "passive"))
    )
    (net (code "19") (name "Net-(Q7-D)") (class "Default")
      (node (ref "Q7") (pin "3") (pinfunction "D_3") (pintype "passive"))
      (node (ref "R42") (pin "1") (pinfunction "1_1") (pintype "passive"))
      (node (ref "R47") (pin "1") (pinfunction "1_1") (pintype "passive"))
      (node (ref "R52") (pin "1") (pinfunction "1_1") (pintype "passive"))
    )
    (net (code "20") (name "Net-(Q7-G)") (class "Default")
      (node (ref "Q7") (pin "1") (pinfunction "G_1") (pintype "passive"))
      (node (ref "R57") (pin "2") (pinfunction "2_2") (pintype "passive"))
      (node (ref "U7") (pin "5") (pinfunction "IOUT_5") (pintype "passive"))
    )
    (net (code "21") (name "Net-(Q7-S)") (class "Default")
      (node (ref "C13") (pin "2") (pinfunction "2_2") (pintype "passive"))
      (node (ref "C18") (pin "2") (pinfunction "2_2") (pintype "passive"))
      (node (ref "CN1") (pin "2") (pinfunction "2_2") (pintype "passive"))
      (node (ref "Q7") (pin "2") (pinfunction "S_2") (pintype "passive"))
      (node (ref "R36") (pin "2") (pinfunction "2_2") (pintype "passive"))
      (node (ref "R57") (pin "1") (pinfunction "1_1") (pintype "passive"))
      (node (ref "U7") (pin "2") (pinfunction "GND_2") (pintype "passive"))
      (node (ref "U7") (pin "3") (pinfunction "SEL_3") (pintype "passive"))
    )
    (net (code "22") (name "Net-(Q8-D)") (class "Default")
      (node (ref "Q8") (pin "3") (pinfunction "D_3") (pintype "passive"))
      (node (ref "R43") (pin "1") (pinfunction "1_1") (pintype "passive"))
      (node (ref "R48") (pin "1") (pinfunction "1_1") (pintype "passive"))
      (node (ref "R53") (pin "1") (pinfunction "1_1") (pintype "passive"))
    )
    (net (code "23") (name "Net-(Q8-G)") (class "Default")
      (node (ref "Q8") (pin "1") (pinfunction "G_1") (pintype "passive"))
      (node (ref "R58") (pin "2") (pinfunction "2_2") (pintype "passive"))
      (node (ref "U8") (pin "5") (pinfunction "IOUT_5") (pintype "passive"))
    )
    (net (code "24") (name "Net-(Q8-S)") (class "Default")
      (node (ref "C13") (pin "1") (pinfunction "1_1") (pintype "passive"))
      (node (ref "C14") (pin "2") (pinfunction "2_2") (pintype "passive"))
      (node (ref "C18") (pin "1") (pinfunction "1_1") (pintype "passive"))
      (node (ref "C19") (pin "2") (pinfunction "2_2") (pintype "passive"))
      (node (ref "Q8") (pin "2") (pinfunction "S_2") (pintype "passive"))
      (node (ref "R36") (pin "1") (pinfunction "1_1") (pintype "passive"))
      (node (ref "R37") (pin "2") (pinfunction "2_2") (pintype "passive"))
      (node (ref "R42") (pin "2") (pinfunction "2_2") (pintype "passive"))
      (node (ref "R47") (pin "2") (pinfunction "2_2") (pintype "passive"))
      (node (ref "R52") (pin "2") (pinfunction "2_2") (pintype "passive"))
      (node (ref "R58") (pin "1") (pinfunction "1_1") (pintype "passive"))
      (node (ref "U7") (pin "1") (pinfunction "VDD_1") (pintype "passive"))
      (node (ref "U8") (pin "2") (pinfunction "GND_2") (pintype "passive"))
      (node (ref "U8") (pin "3") (pinfunction "SEL_3") (pintype "passive"))
    )
    (net (code "25") (name "Net-(Q9-D)") (class "Default")
      (node (ref "Q9") (pin "3") (pinfunction "D_3") (pintype "passive"))
      (node (ref "R44") (pin "1") (pinfunction "1_1") (pintype "passive"))
      (node (ref "R49") (pin "1") (pinfunction "1_1") (pintype "passive"))
      (node (ref "R54") (pin "1") (pinfunction "1_1") (pintype "passive"))
    )
    (net (code "26") (name "Net-(Q9-G)") (class "Default")
      (node (ref "Q9") (pin "1") (pinfunction "G_1") (pintype "passive"))
      (node (ref "R59") (pin "2") (pinfunction "2_2") (pintype "passive"))
      (node (ref "U9") (pin "5") (pinfunction "IOUT_5") (pintype "passive"))
    )
    (net (code "27") (name "Net-(Q9-S)") (class "Default")
      (node (ref "C14") (pin "1") (pinfunction "1_1") (pintype "passive"))
      (node (ref "C15") (pin "2") (pinfunction "2_2") (pintype "passive"))
      (node (ref "C19") (pin "1") (pinfunction "1_1") (pintype "passive"))
      (node (ref "C20") (pin "2") (pinfunction "2_2") (pintype "passive"))
      (node (ref "Q9") (pin "2") (pinfunction "S_2") (pintype "passive"))
      (node (ref "R37") (pin "1") (pinfunction "1_1") (pintype "passive"))
      (node (ref "R38") (pin "2") (pinfunction "2_2") (pintype "passive"))
      (node (ref "R43") (pin "2") (pinfunction "2_2") (pintype "passive"))
      (node (ref "R48") (pin "2") (pinfunction "2_2") (pintype "passive"))
      (node (ref "R53") (pin "2") (pinfunction "2_2") (pintype "passive"))
      (node (ref "R59") (pin "1") (pinfunction "1_1") (pintype "passive"))
      (node (ref "U8") (pin "1") (pinfunction "VDD_1") (pintype "passive"))
      (node (ref "U9") (pin "2") (pinfunction "GND_2") (pintype "passive"))
      (node (ref "U9") (pin "3") (pinfunction "SEL_3") (pintype "passive"))
    )
    (net (code "28") (name "Net-(Q10-D)") (class "Default")
      (node (ref "Q10") (pin "3") (pinfunction "D_3") (pintype "passive"))
      (node (ref "R45") (pin "1") (pinfunction "1_1") (pintype "passive"))
      (node (ref "R50") (pin "1") (pinfunction "1_1") (pintype "passive"))
      (node (ref "R55") (pin "1") (pinfunction "1_1") (pintype "passive"))
    )
    (net (code "29") (name "Net-(Q10-G)") (class "Default")
      (node (ref "Q10") (pin "1") (pinfunction "G_1") (pintype "passive"))
      (node (ref "R60") (pin "2") (pinfunction "2_2") (pintype "passive"))
      (node (ref "U10") (pin "5") (pinfunction "IOUT_5") (pintype "passive"))
    )
    (net (code "30") (name "Net-(Q10-S)") (class "Default")
      (node (ref "C15") (pin "1") (pinfunction "1_1") (pintype "passive"))
      (node (ref "C16") (pin "2") (pinfunction "2_2") (pintype "passive"))
      (node (ref "C20") (pin "1") (pinfunction "1_1") (pintype "passive"))
      (node (ref "C21") (pin "2") (pinfunction "2_2") (pintype "passive"))
      (node (ref "Q10") (pin "2") (pinfunction "S_2") (pintype "passive"))
      (node (ref "R38") (pin "1") (pinfunction "1_1") (pintype "passive"))
      (node (ref "R39") (pin "2") (pinfunction "2_2") (pintype "passive"))
      (node (ref "R44") (pin "2") (pinfunction "2_2") (pintype "passive"))
      (node (ref "R49") (pin "2") (pinfunction "2_2") (pintype "passive"))
      (node (ref "R54") (pin "2") (pinfunction "2_2") (pintype "passive"))
      (node (ref "R60") (pin "1") (pinfunction "1_1") (pintype "passive"))
      (node (ref "U10") (pin "2") (pinfunction "GND_2") (pintype "passive"))
      (node (ref "U10") (pin "3") (pinfunction "SEL_3") (pintype "passive"))
      (node (ref "U9") (pin "1") (pinfunction "VDD_1") (pintype "passive"))
    )
    (net (code "31") (name "Net-(Q11-D)") (class "Default")
      (node (ref "Q11") (pin "3") (pinfunction "D_3") (pintype "passive"))
      (node (ref "R46") (pin "1") (pinfunction "1_1") (pintype "passive"))
      (node (ref "R51") (pin "1") (pinfunction "1_1") (pintype "passive"))
      (node (ref "R56") (pin "1") (pinfunction "1_1") (pintype "passive"))
    )
    (net (code "32") (name "Net-(Q11-G)") (class "Default")
      (node (ref "Q11") (pin "1") (pinfunction "G_1") (pintype "passive"))
      (node (ref "R61") (pin "2") (pinfunction "2_2") (pintype "passive"))
      (node (ref "U11") (pin "5") (pinfunction "IOUT_5") (pintype "passive"))
    )
    (net (code "33") (name "Net-(Q11-S)") (class "Default")
      (node (ref "C16") (pin "1") (pinfunction "1_1") (pintype "passive"))
      (node (ref "C17") (pin "2") (pinfunction "2_2") (pintype "passive"))
      (node (ref "C21") (pin "1") (pinfunction "1_1") (pintype "passive"))
      (node (ref "C22") (pin "2") (pinfunction "2_2") (pintype "passive"))
      (node (ref "Q11") (pin "2") (pinfunction "S_2") (pintype "passive"))
      (node (ref "R39") (pin "1") (pinfunction "1_1") (pintype "passive"))
      (node (ref "R40") (pin "2") (pinfunction "2_2") (pintype "passive"))
      (node (ref "R45") (pin "2") (pinfunction "2_2") (pintype "passive"))
      (node (ref "R50") (pin "2") (pinfunction "2_2") (pintype "passive"))
      (node (ref "R55") (pin "2") (pinfunction "2_2") (pintype "passive"))
      (node (ref "R61") (pin "1") (pinfunction "1_1") (pintype "passive"))
      (node (ref "U10") (pin "1") (pinfunction "VDD_1") (pintype "passive"))
      (node (ref "U11") (pin "2") (pinfunction "GND_2") (pintype "passive"))
      (node (ref "U11") (pin "3") (pinfunction "SEL_3") (pintype "passive"))
    )
    (net (code "34") (name "Net-(U1-VDD)") (class "Default")
      (node (ref "C1") (pin "1") (pinfunction "1_1") (pintype "passive"))
      (node (ref "C6") (pin "1") (pinfunction "1_1") (pintype "passive"))
      (node (ref "CN1") (pin "1") (pinfunction "1_1") (pintype "passive"))
      (node (ref "R11") (pin "2") (pinfunction "2_2") (pintype "passive"))
      (node (ref "R16") (pin "2") (pinfunction "2_2") (pintype "passive"))
      (node (ref "R21") (pin "2") (pinfunction "2_2") (pintype "passive"))
      (node (ref "R26") (pin "1") (pinfunction "1_1") (pintype "passive"))
      (node (ref "U1") (pin "1") (pinfunction "VDD_1") (pintype "passive"))
    )
    (net (code "35") (name "unconnected-(U1-LED-Pad4)") (class "Default")
      (node (ref "U1") (pin "4") (pinfunction "LED_4") (pintype "passive"))
    )
    (net (code "36") (name "unconnected-(U2-LED-Pad4)") (class "Default")
      (node (ref "U2") (pin "4") (pinfunction "LED_4") (pintype "passive"))
    )
    (net (code "37") (name "unconnected-(U3-LED-Pad4)") (class "Default")
      (node (ref "U3") (pin "4") (pinfunction "LED_4") (pintype "passive"))
    )
    (net (code "38") (name "unconnected-(U4-LED-Pad4)") (class "Default")
      (node (ref "U4") (pin "4") (pinfunction "LED_4") (pintype "passive"))
    )
    (net (code "39") (name "unconnected-(U5-LED-Pad4)") (class "Default")
      (node (ref "U5") (pin "4") (pinfunction "LED_4") (pintype "passive"))
    )
    (net (code "40") (name "unconnected-(U6-LED-Pad4)") (class "Default")
      (node (ref "U6") (pin "4") (pinfunction "LED_4") (pintype "passive"))
    )
    (net (code "41") (name "unconnected-(U7-LED-Pad4)") (class "Default")
      (node (ref "U7") (pin "4") (pinfunction "LED_4") (pintype "passive"))
    )
    (net (code "42") (name "unconnected-(U8-LED-Pad4)") (class "Default")
      (node (ref "U8") (pin "4") (pinfunction "LED_4") (pintype "passive"))
    )
    (net (code "43") (name "unconnected-(U9-LED-Pad4)") (class "Default")
      (node (ref "U9") (pin "4") (pinfunction "LED_4") (pintype "passive"))
    )
    (net (code "44") (name "unconnected-(U10-LED-Pad4)") (class "Default")
      (node (ref "U10") (pin "4") (pinfunction "LED_4") (pintype "passive"))
    )
    (net (code "45") (name "unconnected-(U11-LED-Pad4)") (class "Default")
      (node (ref "U11") (pin "4") (pinfunction "LED_4") (pintype "passive"))
    )
  )
)
